# Wozblaster_v1_2.net
KiCad netlist of a schematic drawn in EAGLE
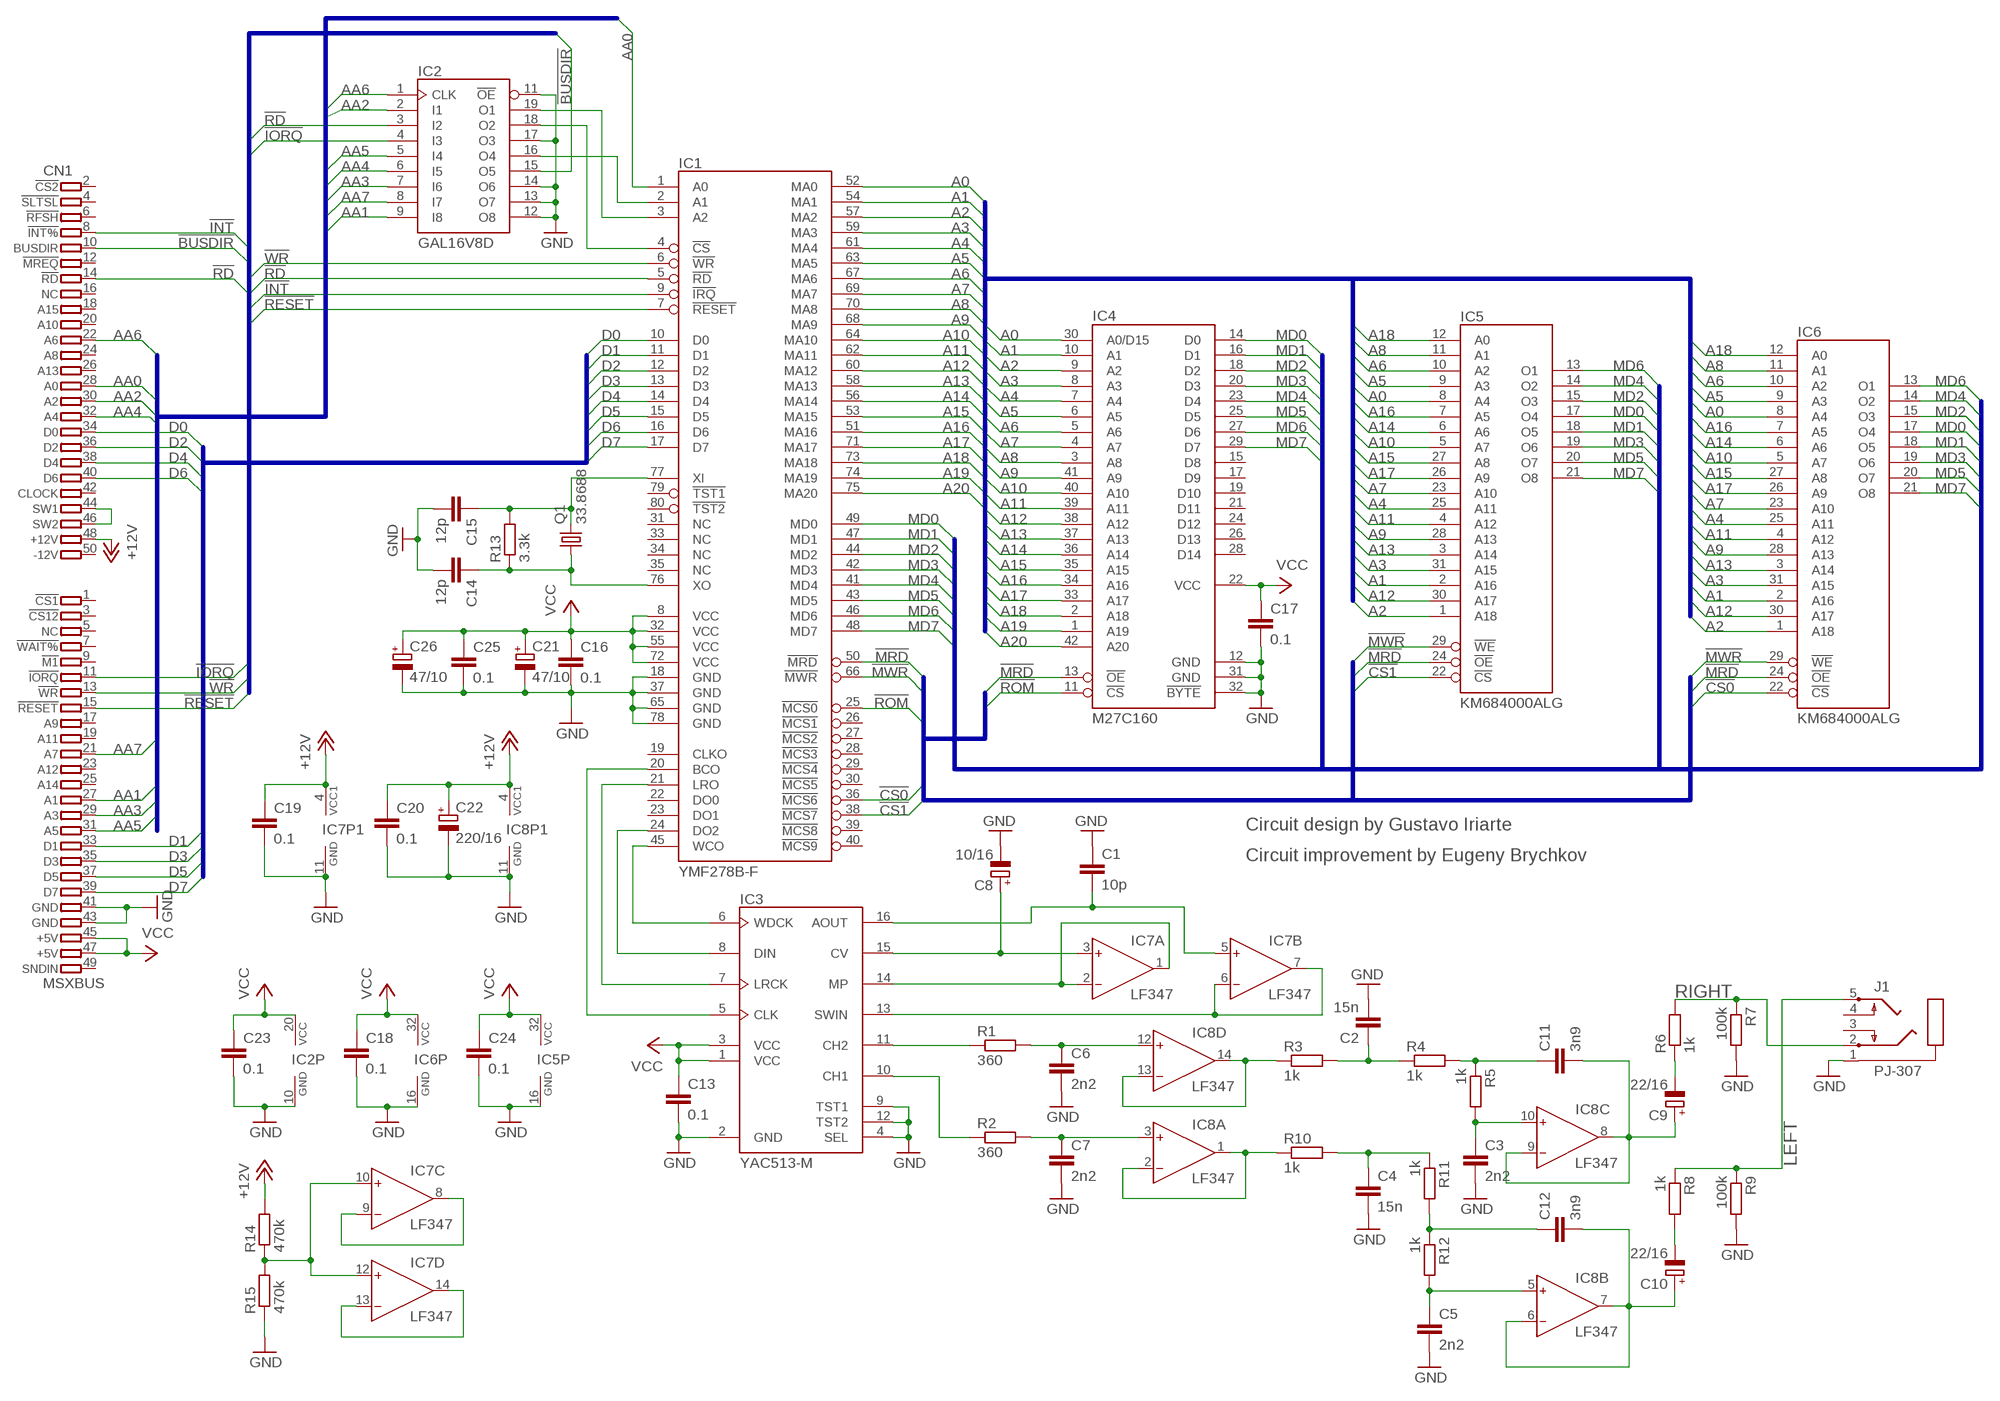
[diagram p0: schematic, sheet 1]

(export (version "E")
  (design (tool "Eeschema 10.0.6"))
  (components
    (comp (ref "C1")
      (value "10p")
      (footprint "eagle-import:C0805")
      (libsource (lib "eagle-import") (part "C-EU"))
    )
    (comp (ref "C2")
      (value "15n")
      (footprint "eagle-import:C0805")
      (libsource (lib "eagle-import") (part "C-EU"))
    )
    (comp (ref "C3")
      (value "2n2")
      (footprint "eagle-import:C0805")
      (libsource (lib "eagle-import") (part "C-EU"))
    )
    (comp (ref "C4")
      (value "15n")
      (footprint "eagle-import:C0805")
      (libsource (lib "eagle-import") (part "C-EU"))
    )
    (comp (ref "C5")
      (value "2n2")
      (footprint "eagle-import:C0805")
      (libsource (lib "eagle-import") (part "C-EU"))
    )
    (comp (ref "C6")
      (value "2n2")
      (footprint "eagle-import:C0805")
      (libsource (lib "eagle-import") (part "C-EU"))
    )
    (comp (ref "C7")
      (value "2n2")
      (footprint "eagle-import:C0805")
      (libsource (lib "eagle-import") (part "C-EU"))
    )
    (comp (ref "C8")
      (value "10/16")
      (footprint "eagle-import:SMC_B")
      (libsource (lib "eagle-import") (part "CPOLSMCB"))
    )
    (comp (ref "C9")
      (value "22/16")
      (footprint "eagle-import:SMC_B")
      (libsource (lib "eagle-import") (part "CPOLSMCB"))
    )
    (comp (ref "C10")
      (value "22/16")
      (footprint "eagle-import:SMC_B")
      (libsource (lib "eagle-import") (part "CPOLSMCB"))
    )
    (comp (ref "C11")
      (value "3n9")
      (footprint "eagle-import:C0805")
      (libsource (lib "eagle-import") (part "C-EU"))
    )
    (comp (ref "C12")
      (value "3n9")
      (footprint "eagle-import:C0805")
      (libsource (lib "eagle-import") (part "C-EU"))
    )
    (comp (ref "C13")
      (value "0.1")
      (footprint "eagle-import:C0805")
      (libsource (lib "eagle-import") (part "C-EU"))
    )
    (comp (ref "C14")
      (value "12p")
      (footprint "eagle-import:C0805")
      (libsource (lib "eagle-import") (part "C-EU"))
    )
    (comp (ref "C15")
      (value "12p")
      (footprint "eagle-import:C0805")
      (libsource (lib "eagle-import") (part "C-EU"))
    )
    (comp (ref "C16")
      (value "0.1")
      (footprint "eagle-import:C0805")
      (libsource (lib "eagle-import") (part "C-EU"))
    )
    (comp (ref "C17")
      (value "0.1")
      (footprint "eagle-import:C0805")
      (libsource (lib "eagle-import") (part "C-EU"))
    )
    (comp (ref "C18")
      (value "0.1")
      (footprint "eagle-import:C0805")
      (libsource (lib "eagle-import") (part "C-EU"))
    )
    (comp (ref "C19")
      (value "0.1")
      (footprint "eagle-import:C0805")
      (libsource (lib "eagle-import") (part "C-EU"))
    )
    (comp (ref "C20")
      (value "0.1")
      (footprint "eagle-import:C0805")
      (libsource (lib "eagle-import") (part "C-EU"))
    )
    (comp (ref "C21")
      (value "47/10")
      (footprint "eagle-import:SMC_B")
      (libsource (lib "eagle-import") (part "CPOLSMCB"))
    )
    (comp (ref "C22")
      (value "220/16")
      (footprint "eagle-import:SMC_E")
      (libsource (lib "eagle-import") (part "CPOLSMCE"))
    )
    (comp (ref "C23")
      (value "0.1")
      (footprint "eagle-import:C0805")
      (libsource (lib "eagle-import") (part "C-EU"))
    )
    (comp (ref "C24")
      (value "0.1")
      (footprint "eagle-import:C0805")
      (libsource (lib "eagle-import") (part "C-EU"))
    )
    (comp (ref "C25")
      (value "0.1")
      (footprint "eagle-import:C0805")
      (libsource (lib "eagle-import") (part "C-EU"))
    )
    (comp (ref "C26")
      (value "47/10")
      (footprint "eagle-import:SMC_B")
      (libsource (lib "eagle-import") (part "CPOLSMCB"))
    )
    (comp (ref "CN1")
      (value "MSXBUS")
      (footprint "eagle-import:MSXBUS_EDGECONN")
      (libsource (lib "eagle-import") (part "MSXBUS_EDGE"))
    )
    (comp (ref "IC1")
      (value "YMF278B-F")
      (footprint "eagle-import:80-QFP")
      (libsource (lib "eagle-import") (part "YMF278B-F"))
    )
    (comp (ref "IC2")
      (value "GAL16V8D")
      (footprint "eagle-import:DIL20")
      (libsource (lib "eagle-import") (part "GAL16V8P3"))
    )
    (comp (ref "IC3")
      (value "YAC513-M")
      (footprint "eagle-import:16SOP")
      (libsource (lib "eagle-import") (part "YAC513-M"))
    )
    (comp (ref "IC4")
      (value "M27C160")
      (footprint "eagle-import:DIL42")
      (libsource (lib "eagle-import") (part "M27C160"))
    )
    (comp (ref "IC5")
      (value "KM684000ALG")
      (footprint "eagle-import:SOP32L")
      (libsource (lib "eagle-import") (part "SRAM4MBIT"))
    )
    (comp (ref "IC6")
      (value "KM684000ALG")
      (footprint "eagle-import:SOP32L")
      (libsource (lib "eagle-import") (part "SRAM4MBIT"))
    )
    (comp (ref "IC7")
      (value "LF347")
      (footprint "eagle-import:SO14-2")
      (libsource (lib "eagle-import") (part "LF347SO14"))
    )
    (comp (ref "IC8")
      (value "LF347")
      (footprint "eagle-import:SO14-2")
      (libsource (lib "eagle-import") (part "LF347SO14"))
    )
    (comp (ref "J1")
      (value "PJ-307")
      (footprint "eagle-import:PJ-307")
      (libsource (lib "eagle-import") (part "PJ-307"))
    )
    (comp (ref "Q1")
      (value "33.8688")
      (footprint "eagle-import:HC49_S")
      (libsource (lib "eagle-import") (part "CRYSTALHC49S"))
    )
    (comp (ref "R1")
      (value "360")
      (footprint "eagle-import:R0805")
      (libsource (lib "eagle-import") (part "R-EU"))
    )
    (comp (ref "R2")
      (value "360")
      (footprint "eagle-import:R0805")
      (libsource (lib "eagle-import") (part "R-EU"))
    )
    (comp (ref "R3")
      (value "1k")
      (footprint "eagle-import:R0805")
      (libsource (lib "eagle-import") (part "R-EU"))
    )
    (comp (ref "R4")
      (value "1k")
      (footprint "eagle-import:R0805")
      (libsource (lib "eagle-import") (part "R-EU"))
    )
    (comp (ref "R5")
      (value "1k")
      (footprint "eagle-import:R0805")
      (libsource (lib "eagle-import") (part "R-EU"))
    )
    (comp (ref "R6")
      (value "1k")
      (footprint "eagle-import:R0805")
      (libsource (lib "eagle-import") (part "R-EU"))
    )
    (comp (ref "R7")
      (value "100k")
      (footprint "eagle-import:R0805")
      (libsource (lib "eagle-import") (part "R-EU"))
    )
    (comp (ref "R8")
      (value "1k")
      (footprint "eagle-import:R0805")
      (libsource (lib "eagle-import") (part "R-EU"))
    )
    (comp (ref "R9")
      (value "100k")
      (footprint "eagle-import:R0805")
      (libsource (lib "eagle-import") (part "R-EU"))
    )
    (comp (ref "R10")
      (value "1k")
      (footprint "eagle-import:R0805")
      (libsource (lib "eagle-import") (part "R-EU"))
    )
    (comp (ref "R11")
      (value "1k")
      (footprint "eagle-import:R0805")
      (libsource (lib "eagle-import") (part "R-EU"))
    )
    (comp (ref "R12")
      (value "1k")
      (footprint "eagle-import:R0805")
      (libsource (lib "eagle-import") (part "R-EU"))
    )
    (comp (ref "R13")
      (value "3.3k")
      (footprint "eagle-import:R0805")
      (libsource (lib "eagle-import") (part "R-EU"))
    )
    (comp (ref "R14")
      (value "470k")
      (footprint "eagle-import:R0805")
      (libsource (lib "eagle-import") (part "R-EU"))
    )
    (comp (ref "R15")
      (value "470k")
      (footprint "eagle-import:R0805")
      (libsource (lib "eagle-import") (part "R-EU"))
    )
  )
  (nets
    (net (code "1") (name "+12V") (class "Default")
      (node (ref "C19") (pin "1") (pinfunction "1_1") (pintype "passive"))
      (node (ref "C20") (pin "1") (pinfunction "1_1") (pintype "passive"))
      (node (ref "C22") (pin "+") (pinfunction "+_+") (pintype "passive"))
      (node (ref "CN1") (pin "48") (pinfunction "48.+12V_48") (pintype "passive"))
      (node (ref "IC7") (pin "4") (pinfunction "VCC_4") (pintype "power_in"))
      (node (ref "IC8") (pin "4") (pinfunction "VCC_4") (pintype "power_in"))
      (node (ref "R14") (pin "2") (pinfunction "2_2") (pintype "passive"))
    )
    (net (code "2") (name "/A0") (class "Default")
      (node (ref "IC1") (pin "52") (pinfunction "MA0_52") (pintype "output"))
      (node (ref "IC4") (pin "30") (pinfunction "A0/D15_30") (pintype "passive"))
      (node (ref "IC5") (pin "8") (pinfunction "A4_8") (pintype "bidirectional"))
      (node (ref "IC6") (pin "8") (pinfunction "A4_8") (pintype "bidirectional"))
    )
    (net (code "3") (name "/A1") (class "Default")
      (node (ref "IC1") (pin "54") (pinfunction "MA1_54") (pintype "output"))
      (node (ref "IC4") (pin "10") (pinfunction "A1_10") (pintype "passive"))
      (node (ref "IC5") (pin "2") (pinfunction "A16_2") (pintype "bidirectional"))
      (node (ref "IC6") (pin "2") (pinfunction "A16_2") (pintype "bidirectional"))
    )
    (net (code "4") (name "/A2") (class "Default")
      (node (ref "IC1") (pin "57") (pinfunction "MA2_57") (pintype "output"))
      (node (ref "IC4") (pin "9") (pinfunction "A2_9") (pintype "passive"))
      (node (ref "IC5") (pin "1") (pinfunction "A18_1") (pintype "bidirectional"))
      (node (ref "IC6") (pin "1") (pinfunction "A18_1") (pintype "bidirectional"))
    )
    (net (code "5") (name "/A3") (class "Default")
      (node (ref "IC1") (pin "59") (pinfunction "MA3_59") (pintype "output"))
      (node (ref "IC4") (pin "8") (pinfunction "A3_8") (pintype "passive"))
      (node (ref "IC5") (pin "31") (pinfunction "A15_31") (pintype "bidirectional"))
      (node (ref "IC6") (pin "31") (pinfunction "A15_31") (pintype "bidirectional"))
    )
    (net (code "6") (name "/A4") (class "Default")
      (node (ref "IC1") (pin "61") (pinfunction "MA4_61") (pintype "output"))
      (node (ref "IC4") (pin "7") (pinfunction "A4_7") (pintype "passive"))
      (node (ref "IC5") (pin "25") (pinfunction "A11_25") (pintype "bidirectional"))
      (node (ref "IC6") (pin "25") (pinfunction "A11_25") (pintype "bidirectional"))
    )
    (net (code "7") (name "/A5") (class "Default")
      (node (ref "IC1") (pin "63") (pinfunction "MA5_63") (pintype "output"))
      (node (ref "IC4") (pin "6") (pinfunction "A5_6") (pintype "passive"))
      (node (ref "IC5") (pin "9") (pinfunction "A3_9") (pintype "bidirectional"))
      (node (ref "IC6") (pin "9") (pinfunction "A3_9") (pintype "bidirectional"))
    )
    (net (code "8") (name "/A6") (class "Default")
      (node (ref "IC1") (pin "67") (pinfunction "MA6_67") (pintype "output"))
      (node (ref "IC4") (pin "5") (pinfunction "A6_5") (pintype "passive"))
      (node (ref "IC5") (pin "10") (pinfunction "A2_10") (pintype "bidirectional"))
      (node (ref "IC6") (pin "10") (pinfunction "A2_10") (pintype "bidirectional"))
    )
    (net (code "9") (name "/A7") (class "Default")
      (node (ref "IC1") (pin "69") (pinfunction "MA7_69") (pintype "output"))
      (node (ref "IC4") (pin "4") (pinfunction "A7_4") (pintype "passive"))
      (node (ref "IC5") (pin "23") (pinfunction "A10_23") (pintype "bidirectional"))
      (node (ref "IC6") (pin "23") (pinfunction "A10_23") (pintype "bidirectional"))
    )
    (net (code "10") (name "/A8") (class "Default")
      (node (ref "IC1") (pin "70") (pinfunction "MA8_70") (pintype "output"))
      (node (ref "IC4") (pin "3") (pinfunction "A8_3") (pintype "passive"))
      (node (ref "IC5") (pin "11") (pinfunction "A1_11") (pintype "bidirectional"))
      (node (ref "IC6") (pin "11") (pinfunction "A1_11") (pintype "bidirectional"))
    )
    (net (code "11") (name "/A9") (class "Default")
      (node (ref "IC1") (pin "68") (pinfunction "MA9_68") (pintype "output"))
      (node (ref "IC4") (pin "41") (pinfunction "A9_41") (pintype "passive"))
      (node (ref "IC5") (pin "28") (pinfunction "A13_28") (pintype "bidirectional"))
      (node (ref "IC6") (pin "28") (pinfunction "A13_28") (pintype "bidirectional"))
    )
    (net (code "12") (name "/A10") (class "Default")
      (node (ref "IC1") (pin "64") (pinfunction "MA10_64") (pintype "output"))
      (node (ref "IC4") (pin "40") (pinfunction "A10_40") (pintype "passive"))
      (node (ref "IC5") (pin "5") (pinfunction "A7_5") (pintype "bidirectional"))
      (node (ref "IC6") (pin "5") (pinfunction "A7_5") (pintype "bidirectional"))
    )
    (net (code "13") (name "/A11") (class "Default")
      (node (ref "IC1") (pin "62") (pinfunction "MA11_62") (pintype "output"))
      (node (ref "IC4") (pin "39") (pinfunction "A11_39") (pintype "passive"))
      (node (ref "IC5") (pin "4") (pinfunction "A12_4") (pintype "bidirectional"))
      (node (ref "IC6") (pin "4") (pinfunction "A12_4") (pintype "bidirectional"))
    )
    (net (code "14") (name "/A12") (class "Default")
      (node (ref "IC1") (pin "60") (pinfunction "MA12_60") (pintype "output"))
      (node (ref "IC4") (pin "38") (pinfunction "A12_38") (pintype "passive"))
      (node (ref "IC5") (pin "30") (pinfunction "A17_30") (pintype "bidirectional"))
      (node (ref "IC6") (pin "30") (pinfunction "A17_30") (pintype "bidirectional"))
    )
    (net (code "15") (name "/A13") (class "Default")
      (node (ref "IC1") (pin "58") (pinfunction "MA13_58") (pintype "output"))
      (node (ref "IC4") (pin "37") (pinfunction "A13_37") (pintype "passive"))
      (node (ref "IC5") (pin "3") (pinfunction "A14_3") (pintype "bidirectional"))
      (node (ref "IC6") (pin "3") (pinfunction "A14_3") (pintype "bidirectional"))
    )
    (net (code "16") (name "/A14") (class "Default")
      (node (ref "IC1") (pin "56") (pinfunction "MA14_56") (pintype "output"))
      (node (ref "IC4") (pin "36") (pinfunction "A14_36") (pintype "passive"))
      (node (ref "IC5") (pin "6") (pinfunction "A6_6") (pintype "bidirectional"))
      (node (ref "IC6") (pin "6") (pinfunction "A6_6") (pintype "bidirectional"))
    )
    (net (code "17") (name "/A15") (class "Default")
      (node (ref "IC1") (pin "53") (pinfunction "MA15_53") (pintype "output"))
      (node (ref "IC4") (pin "35") (pinfunction "A15_35") (pintype "passive"))
      (node (ref "IC5") (pin "27") (pinfunction "A8_27") (pintype "bidirectional"))
      (node (ref "IC6") (pin "27") (pinfunction "A8_27") (pintype "bidirectional"))
    )
    (net (code "18") (name "/A16") (class "Default")
      (node (ref "IC1") (pin "51") (pinfunction "MA16_51") (pintype "output"))
      (node (ref "IC4") (pin "34") (pinfunction "A16_34") (pintype "passive"))
      (node (ref "IC5") (pin "7") (pinfunction "A5_7") (pintype "bidirectional"))
      (node (ref "IC6") (pin "7") (pinfunction "A5_7") (pintype "bidirectional"))
    )
    (net (code "19") (name "/A17") (class "Default")
      (node (ref "IC1") (pin "71") (pinfunction "MA17_71") (pintype "output"))
      (node (ref "IC4") (pin "33") (pinfunction "A17_33") (pintype "passive"))
      (node (ref "IC5") (pin "26") (pinfunction "A9_26") (pintype "bidirectional"))
      (node (ref "IC6") (pin "26") (pinfunction "A9_26") (pintype "bidirectional"))
    )
    (net (code "20") (name "/A18") (class "Default")
      (node (ref "IC1") (pin "73") (pinfunction "MA18_73") (pintype "output"))
      (node (ref "IC4") (pin "2") (pinfunction "A18_2") (pintype "passive"))
      (node (ref "IC5") (pin "12") (pinfunction "A0_12") (pintype "bidirectional"))
      (node (ref "IC6") (pin "12") (pinfunction "A0_12") (pintype "bidirectional"))
    )
    (net (code "21") (name "/A19") (class "Default")
      (node (ref "IC1") (pin "74") (pinfunction "MA19_74") (pintype "output"))
      (node (ref "IC4") (pin "1") (pinfunction "A19_1") (pintype "passive"))
    )
    (net (code "22") (name "/A20") (class "Default")
      (node (ref "IC1") (pin "75") (pinfunction "MA20_75") (pintype "output"))
      (node (ref "IC4") (pin "42") (pinfunction "A20_42") (pintype "passive"))
    )
    (net (code "23") (name "/AA0") (class "Default")
      (node (ref "CN1") (pin "28") (pinfunction "28.A0_28") (pintype "output"))
      (node (ref "IC1") (pin "1") (pinfunction "A0_1") (pintype "input"))
    )
    (net (code "24") (name "/AA1") (class "Default")
      (node (ref "CN1") (pin "27") (pinfunction "27.A1_27") (pintype "output"))
      (node (ref "IC2") (pin "9") (pinfunction "I8_9") (pintype "input"))
    )
    (net (code "25") (name "/AA2") (class "Default")
      (node (ref "CN1") (pin "30") (pinfunction "30.A2_30") (pintype "output"))
      (node (ref "IC2") (pin "2") (pinfunction "I1_2") (pintype "input"))
    )
    (net (code "26") (name "/AA3") (class "Default")
      (node (ref "CN1") (pin "29") (pinfunction "29.A3_29") (pintype "output"))
      (node (ref "IC2") (pin "7") (pinfunction "I6_7") (pintype "input"))
    )
    (net (code "27") (name "/AA4") (class "Default")
      (node (ref "CN1") (pin "32") (pinfunction "32.A4_32") (pintype "output"))
      (node (ref "IC2") (pin "6") (pinfunction "I5_6") (pintype "input"))
    )
    (net (code "28") (name "/AA5") (class "Default")
      (node (ref "CN1") (pin "31") (pinfunction "31.A5_31") (pintype "output"))
      (node (ref "IC2") (pin "5") (pinfunction "I4_5") (pintype "input"))
    )
    (net (code "29") (name "/AA6") (class "Default")
      (node (ref "CN1") (pin "22") (pinfunction "22.A6_22") (pintype "output"))
      (node (ref "IC2") (pin "1") (pinfunction "CLK_1") (pintype "input"))
    )
    (net (code "30") (name "/AA7") (class "Default")
      (node (ref "CN1") (pin "21") (pinfunction "21.A7_21") (pintype "output"))
      (node (ref "IC2") (pin "8") (pinfunction "I7_8") (pintype "input"))
    )
    (net (code "31") (name "/D0") (class "Default")
      (node (ref "CN1") (pin "34") (pinfunction "34.D0_34") (pintype "bidirectional"))
      (node (ref "IC1") (pin "10") (pinfunction "D0_10") (pintype "bidirectional"))
    )
    (net (code "32") (name "/D1") (class "Default")
      (node (ref "CN1") (pin "33") (pinfunction "33.D1_33") (pintype "bidirectional"))
      (node (ref "IC1") (pin "11") (pinfunction "D1_11") (pintype "bidirectional"))
    )
    (net (code "33") (name "/D2") (class "Default")
      (node (ref "CN1") (pin "36") (pinfunction "36.D2_36") (pintype "bidirectional"))
      (node (ref "IC1") (pin "12") (pinfunction "D2_12") (pintype "bidirectional"))
    )
    (net (code "34") (name "/D3") (class "Default")
      (node (ref "CN1") (pin "35") (pinfunction "35.D3_35") (pintype "bidirectional"))
      (node (ref "IC1") (pin "13") (pinfunction "D3_13") (pintype "bidirectional"))
    )
    (net (code "35") (name "/D4") (class "Default")
      (node (ref "CN1") (pin "38") (pinfunction "38.D4_38") (pintype "bidirectional"))
      (node (ref "IC1") (pin "14") (pinfunction "D4_14") (pintype "bidirectional"))
    )
    (net (code "36") (name "/D5") (class "Default")
      (node (ref "CN1") (pin "37") (pinfunction "37.D5_37") (pintype "bidirectional"))
      (node (ref "IC1") (pin "15") (pinfunction "D5_15") (pintype "bidirectional"))
    )
    (net (code "37") (name "/D6") (class "Default")
      (node (ref "CN1") (pin "40") (pinfunction "40.D6_40") (pintype "bidirectional"))
      (node (ref "IC1") (pin "16") (pinfunction "D6_16") (pintype "bidirectional"))
    )
    (net (code "38") (name "/D7") (class "Default")
      (node (ref "CN1") (pin "39") (pinfunction "39.D7_39") (pintype "bidirectional"))
      (node (ref "IC1") (pin "17") (pinfunction "D7_17") (pintype "bidirectional"))
    )
    (net (code "39") (name "/MD0") (class "Default")
      (node (ref "IC1") (pin "49") (pinfunction "MD0_49") (pintype "bidirectional"))
      (node (ref "IC4") (pin "14") (pinfunction "D0_14") (pintype "passive"))
      (node (ref "IC5") (pin "17") (pinfunction "O4_17") (pintype "bidirectional"))
      (node (ref "IC6") (pin "17") (pinfunction "O4_17") (pintype "bidirectional"))
    )
    (net (code "40") (name "/MD1") (class "Default")
      (node (ref "IC1") (pin "47") (pinfunction "MD1_47") (pintype "bidirectional"))
      (node (ref "IC4") (pin "16") (pinfunction "D1_16") (pintype "passive"))
      (node (ref "IC5") (pin "18") (pinfunction "O5_18") (pintype "bidirectional"))
      (node (ref "IC6") (pin "18") (pinfunction "O5_18") (pintype "bidirectional"))
    )
    (net (code "41") (name "/MD2") (class "Default")
      (node (ref "IC1") (pin "44") (pinfunction "MD2_44") (pintype "bidirectional"))
      (node (ref "IC4") (pin "18") (pinfunction "D2_18") (pintype "passive"))
      (node (ref "IC5") (pin "15") (pinfunction "O3_15") (pintype "bidirectional"))
      (node (ref "IC6") (pin "15") (pinfunction "O3_15") (pintype "bidirectional"))
    )
    (net (code "42") (name "/MD3") (class "Default")
      (node (ref "IC1") (pin "42") (pinfunction "MD3_42") (pintype "bidirectional"))
      (node (ref "IC4") (pin "20") (pinfunction "D3_20") (pintype "passive"))
      (node (ref "IC5") (pin "19") (pinfunction "O6_19") (pintype "bidirectional"))
      (node (ref "IC6") (pin "19") (pinfunction "O6_19") (pintype "bidirectional"))
    )
    (net (code "43") (name "/MD4") (class "Default")
      (node (ref "IC1") (pin "41") (pinfunction "MD4_41") (pintype "bidirectional"))
      (node (ref "IC4") (pin "23") (pinfunction "D4_23") (pintype "passive"))
      (node (ref "IC5") (pin "14") (pinfunction "O2_14") (pintype "bidirectional"))
      (node (ref "IC6") (pin "14") (pinfunction "O2_14") (pintype "bidirectional"))
    )
    (net (code "44") (name "/MD5") (class "Default")
      (node (ref "IC1") (pin "43") (pinfunction "MD5_43") (pintype "bidirectional"))
      (node (ref "IC4") (pin "25") (pinfunction "D5_25") (pintype "passive"))
      (node (ref "IC5") (pin "20") (pinfunction "O7_20") (pintype "bidirectional"))
      (node (ref "IC6") (pin "20") (pinfunction "O7_20") (pintype "bidirectional"))
    )
    (net (code "45") (name "/MD6") (class "Default")
      (node (ref "IC1") (pin "46") (pinfunction "MD6_46") (pintype "bidirectional"))
      (node (ref "IC4") (pin "27") (pinfunction "D6_27") (pintype "passive"))
      (node (ref "IC5") (pin "13") (pinfunction "O1_13") (pintype "bidirectional"))
      (node (ref "IC6") (pin "13") (pinfunction "O1_13") (pintype "bidirectional"))
    )
    (net (code "46") (name "/MD7") (class "Default")
      (node (ref "IC1") (pin "48") (pinfunction "MD7_48") (pintype "bidirectional"))
      (node (ref "IC4") (pin "29") (pinfunction "D7_29") (pintype "passive"))
      (node (ref "IC5") (pin "21") (pinfunction "O8_21") (pintype "bidirectional"))
      (node (ref "IC6") (pin "21") (pinfunction "O8_21") (pintype "bidirectional"))
    )
    (net (code "47") (name "/~{BUSDIR}") (class "Default")
      (node (ref "CN1") (pin "10") (pinfunction "10.BUSDIR_10") (pintype "open_collector"))
      (node (ref "IC2") (pin "15") (pinfunction "O5_15") (pintype "tri_state"))
    )
    (net (code "48") (name "/~{CS0}") (class "Default")
      (node (ref "IC1") (pin "36") (pinfunction "~{MCS6}_36") (pintype "output"))
      (node (ref "IC6") (pin "22") (pinfunction "~{CS}_22") (pintype "bidirectional"))
    )
    (net (code "49") (name "/~{CS1}") (class "Default")
      (node (ref "IC1") (pin "38") (pinfunction "~{MCS7}_38") (pintype "output"))
      (node (ref "IC5") (pin "22") (pinfunction "~{CS}_22") (pintype "bidirectional"))
    )
    (net (code "50") (name "/~{INT}") (class "Default")
      (node (ref "CN1") (pin "8") (pinfunction "8.~{INT%}_8") (pintype "open_collector"))
      (node (ref "IC1") (pin "9") (pinfunction "~{IRQ}_9") (pintype "bidirectional"))
    )
    (net (code "51") (name "/~{IORQ}") (class "Default")
      (node (ref "CN1") (pin "11") (pinfunction "11.~{IORQ}_11") (pintype "output"))
      (node (ref "IC2") (pin "4") (pinfunction "I3_4") (pintype "input"))
    )
    (net (code "52") (name "/~{MRD}") (class "Default")
      (node (ref "IC1") (pin "50") (pinfunction "~{MRD}_50") (pintype "output"))
      (node (ref "IC4") (pin "13") (pinfunction "~{OE}_13") (pintype "passive"))
      (node (ref "IC5") (pin "24") (pinfunction "~{OE}_24") (pintype "bidirectional"))
      (node (ref "IC6") (pin "24") (pinfunction "~{OE}_24") (pintype "bidirectional"))
    )
    (net (code "53") (name "/~{MWR}") (class "Default")
      (node (ref "IC1") (pin "66") (pinfunction "~{MWR}_66") (pintype "output"))
      (node (ref "IC5") (pin "29") (pinfunction "~{WE}_29") (pintype "bidirectional"))
      (node (ref "IC6") (pin "29") (pinfunction "~{WE}_29") (pintype "bidirectional"))
    )
    (net (code "54") (name "/~{RD}") (class "Default")
      (node (ref "CN1") (pin "14") (pinfunction "14.~{RD}_14") (pintype "output"))
      (node (ref "IC1") (pin "5") (pinfunction "~{RD}_5") (pintype "input"))
      (node (ref "IC2") (pin "3") (pinfunction "I2_3") (pintype "input"))
    )
    (net (code "55") (name "/~{RESET}") (class "Default")
      (node (ref "CN1") (pin "15") (pinfunction "15.~{RESET}_15") (pintype "output"))
      (node (ref "IC1") (pin "7") (pinfunction "~{RESET}_7") (pintype "input"))
    )
    (net (code "56") (name "/~{ROM}") (class "Default")
      (node (ref "IC1") (pin "25") (pinfunction "~{MCS0}_25") (pintype "output"))
      (node (ref "IC4") (pin "11") (pinfunction "~{CS}_11") (pintype "passive"))
    )
    (net (code "57") (name "/~{WR}") (class "Default")
      (node (ref "CN1") (pin "13") (pinfunction "13.~{WR}_13") (pintype "output"))
      (node (ref "IC1") (pin "6") (pinfunction "~{WR}_6") (pintype "input"))
    )
    (net (code "58") (name "GND") (class "Default")
      (node (ref "C1") (pin "1") (pinfunction "1_1") (pintype "passive"))
      (node (ref "C13") (pin "2") (pinfunction "2_2") (pintype "passive"))
      (node (ref "C14") (pin "2") (pinfunction "2_2") (pintype "passive"))
      (node (ref "C15") (pin "2") (pinfunction "2_2") (pintype "passive"))
      (node (ref "C16") (pin "2") (pinfunction "2_2") (pintype "passive"))
      (node (ref "C17") (pin "2") (pinfunction "2_2") (pintype "passive"))
      (node (ref "C18") (pin "2") (pinfunction "2_2") (pintype "passive"))
      (node (ref "C19") (pin "2") (pinfunction "2_2") (pintype "passive"))
      (node (ref "C2") (pin "2") (pinfunction "2_2") (pintype "passive"))
      (node (ref "C20") (pin "2") (pinfunction "2_2") (pintype "passive"))
      (node (ref "C21") (pin "-") (pinfunction "-_-") (pintype "passive"))
      (node (ref "C22") (pin "-") (pinfunction "-_-") (pintype "passive"))
      (node (ref "C23") (pin "2") (pinfunction "2_2") (pintype "passive"))
      (node (ref "C24") (pin "2") (pinfunction "2_2") (pintype "passive"))
      (node (ref "C25") (pin "2") (pinfunction "2_2") (pintype "passive"))
      (node (ref "C26") (pin "-") (pinfunction "-_-") (pintype "passive"))
      (node (ref "C3") (pin "2") (pinfunction "2_2") (pintype "passive"))
      (node (ref "C4") (pin "2") (pinfunction "2_2") (pintype "passive"))
      (node (ref "C5") (pin "2") (pinfunction "2_2") (pintype "passive"))
      (node (ref "C6") (pin "2") (pinfunction "2_2") (pintype "passive"))
      (node (ref "C7") (pin "2") (pinfunction "2_2") (pintype "passive"))
      (node (ref "C8") (pin "-") (pinfunction "-_-") (pintype "passive"))
      (node (ref "CN1") (pin "41") (pinfunction "41.GND_41") (pintype "passive"))
      (node (ref "CN1") (pin "43") (pinfunction "43.GND_43") (pintype "passive"))
      (node (ref "IC1") (pin "18") (pinfunction "GND_18") (pintype "bidirectional"))
      (node (ref "IC1") (pin "37") (pinfunction "GND_37") (pintype "bidirectional"))
      (node (ref "IC1") (pin "65") (pinfunction "GND_65") (pintype "bidirectional"))
      (node (ref "IC1") (pin "78") (pinfunction "GND_78") (pintype "bidirectional"))
      (node (ref "IC2") (pin "10") (pinfunction "GND_10") (pintype "power_in"))
      (node (ref "IC2") (pin "11") (pinfunction "~{OE}_11") (pintype "input"))
      (node (ref "IC2") (pin "12") (pinfunction "O8_12") (pintype "tri_state"))
      (node (ref "IC2") (pin "13") (pinfunction "O7_13") (pintype "tri_state"))
      (node (ref "IC2") (pin "14") (pinfunction "O6_14") (pintype "tri_state"))
      (node (ref "IC2") (pin "17") (pinfunction "O3_17") (pintype "tri_state"))
      (node (ref "IC3") (pin "12") (pinfunction "TST2_12") (pintype "input"))
      (node (ref "IC3") (pin "2") (pinfunction "GND_2") (pintype "power_in"))
      (node (ref "IC3") (pin "4") (pinfunction "SEL_4") (pintype "input"))
      (node (ref "IC3") (pin "9") (pinfunction "TST1_9") (pintype "input"))
      (node (ref "IC4") (pin "12") (pinfunction "GND_12") (pintype "passive"))
      (node (ref "IC4") (pin "31") (pinfunction "GND_31") (pintype "passive"))
      (node (ref "IC4") (pin "32") (pinfunction "~{BYTE}_32") (pintype "passive"))
      (node (ref "IC5") (pin "16") (pinfunction "GND_16") (pintype "power_in"))
      (node (ref "IC6") (pin "16") (pinfunction "GND_16") (pintype "power_in"))
      (node (ref "IC7") (pin "11") (pinfunction "GND_11") (pintype "power_in"))
      (node (ref "IC8") (pin "11") (pinfunction "GND_11") (pintype "power_in"))
      (node (ref "J1") (pin "1") (pinfunction "1_1") (pintype "passive"))
      (node (ref "R15") (pin "1") (pinfunction "1_1") (pintype "passive"))
      (node (ref "R7") (pin "2") (pinfunction "2_2") (pintype "passive"))
      (node (ref "R9") (pin "2") (pinfunction "2_2") (pintype "passive"))
    )
    (net (code "59") (name "Net-(C2-Pad1)") (class "Default")
      (node (ref "C2") (pin "1") (pinfunction "1_1") (pintype "passive"))
      (node (ref "R3") (pin "2") (pinfunction "2_2") (pintype "passive"))
      (node (ref "R4") (pin "1") (pinfunction "1_1") (pintype "passive"))
    )
    (net (code "60") (name "Net-(C4-Pad1)") (class "Default")
      (node (ref "C4") (pin "1") (pinfunction "1_1") (pintype "passive"))
      (node (ref "R10") (pin "2") (pinfunction "2_2") (pintype "passive"))
      (node (ref "R11") (pin "1") (pinfunction "1_1") (pintype "passive"))
    )
    (net (code "61") (name "Net-(C9-Pad-)") (class "Default")
      (node (ref "C9") (pin "-") (pinfunction "-_-") (pintype "passive"))
      (node (ref "R6") (pin "1") (pinfunction "1_1") (pintype "passive"))
    )
    (net (code "62") (name "Net-(C10-Pad-)") (class "Default")
      (node (ref "C10") (pin "-") (pinfunction "-_-") (pintype "passive"))
      (node (ref "R8") (pin "2") (pinfunction "2_2") (pintype "passive"))
    )
    (net (code "63") (name "Net-(C11-Pad1)") (class "Default")
      (node (ref "C11") (pin "1") (pinfunction "1_1") (pintype "passive"))
      (node (ref "R4") (pin "2") (pinfunction "2_2") (pintype "passive"))
      (node (ref "R5") (pin "1") (pinfunction "1_1") (pintype "passive"))
    )
    (net (code "64") (name "Net-(C12-Pad1)") (class "Default")
      (node (ref "C12") (pin "1") (pinfunction "1_1") (pintype "passive"))
      (node (ref "R11") (pin "2") (pinfunction "2_2") (pintype "passive"))
      (node (ref "R12") (pin "1") (pinfunction "1_1") (pintype "passive"))
    )
    (net (code "65") (name "Net-(CN1-44.SW1)") (class "Default")
      (node (ref "CN1") (pin "44") (pinfunction "44.SW1_44") (pintype "passive"))
      (node (ref "CN1") (pin "46") (pinfunction "46.SW2_46") (pintype "passive"))
    )
    (net (code "66") (name "Net-(IC1-A1)") (class "Default")
      (node (ref "IC1") (pin "2") (pinfunction "A1_2") (pintype "input"))
      (node (ref "IC2") (pin "16") (pinfunction "O4_16") (pintype "tri_state"))
    )
    (net (code "67") (name "Net-(IC1-A2)") (class "Default")
      (node (ref "IC1") (pin "3") (pinfunction "A2_3") (pintype "input"))
      (node (ref "IC2") (pin "19") (pinfunction "O1_19") (pintype "tri_state"))
    )
    (net (code "68") (name "Net-(IC1-BCO)") (class "Default")
      (node (ref "IC1") (pin "20") (pinfunction "BCO_20") (pintype "output"))
      (node (ref "IC3") (pin "5") (pinfunction "CLK_5") (pintype "input"))
    )
    (net (code "69") (name "Net-(IC1-DO2)") (class "Default")
      (node (ref "IC1") (pin "24") (pinfunction "DO2_24") (pintype "output"))
      (node (ref "IC3") (pin "8") (pinfunction "DIN_8") (pintype "input"))
    )
    (net (code "70") (name "Net-(IC1-LRO)") (class "Default")
      (node (ref "IC1") (pin "21") (pinfunction "LRO_21") (pintype "output"))
      (node (ref "IC3") (pin "7") (pinfunction "LRCK_7") (pintype "input"))
    )
    (net (code "71") (name "Net-(IC1-WCO)") (class "Default")
      (node (ref "IC1") (pin "45") (pinfunction "WCO_45") (pintype "output"))
      (node (ref "IC3") (pin "6") (pinfunction "WDCK_6") (pintype "input"))
    )
    (net (code "72") (name "Net-(IC1-XI)") (class "Default")
      (node (ref "C15") (pin "1") (pinfunction "1_1") (pintype "passive"))
      (node (ref "IC1") (pin "77") (pinfunction "XI_77") (pintype "input"))
      (node (ref "Q1") (pin "2") (pinfunction "2_2") (pintype "passive"))
      (node (ref "R13") (pin "2") (pinfunction "2_2") (pintype "passive"))
    )
    (net (code "73") (name "Net-(IC1-XO)") (class "Default")
      (node (ref "C14") (pin "1") (pinfunction "1_1") (pintype "passive"))
      (node (ref "IC1") (pin "76") (pinfunction "XO_76") (pintype "output"))
      (node (ref "Q1") (pin "1") (pinfunction "1_1") (pintype "passive"))
      (node (ref "R13") (pin "1") (pinfunction "1_1") (pintype "passive"))
    )
    (net (code "74") (name "Net-(IC1-~{CS})") (class "Default")
      (node (ref "IC1") (pin "4") (pinfunction "~{CS}_4") (pintype "input"))
      (node (ref "IC2") (pin "18") (pinfunction "O2_18") (pintype "tri_state"))
    )
    (net (code "75") (name "Net-(IC3-AOUT)") (class "Default")
      (node (ref "C1") (pin "2") (pinfunction "2_2") (pintype "passive"))
      (node (ref "IC3") (pin "16") (pinfunction "AOUT_16") (pintype "output"))
      (node (ref "IC7") (pin "5") (pinfunction "IN+_5") (pintype "input"))
    )
    (net (code "76") (name "Net-(IC3-CH1)") (class "Default")
      (node (ref "IC3") (pin "10") (pinfunction "CH1_10") (pintype "output"))
      (node (ref "R2") (pin "1") (pinfunction "1_1") (pintype "passive"))
    )
    (net (code "77") (name "Net-(IC3-CH2)") (class "Default")
      (node (ref "IC3") (pin "11") (pinfunction "CH2_11") (pintype "output"))
      (node (ref "R1") (pin "1") (pinfunction "1_1") (pintype "passive"))
    )
    (net (code "78") (name "Net-(IC3-CV)") (class "Default")
      (node (ref "C8") (pin "+") (pinfunction "+_+") (pintype "passive"))
      (node (ref "IC3") (pin "15") (pinfunction "CV_15") (pintype "input"))
      (node (ref "IC7") (pin "3") (pinfunction "IN+_3") (pintype "input"))
    )
    (net (code "79") (name "Net-(IC3-MP)") (class "Default")
      (node (ref "IC3") (pin "14") (pinfunction "MP_14") (pintype "input"))
      (node (ref "IC7") (pin "1") (pinfunction "OUT_1") (pintype "output"))
      (node (ref "IC7") (pin "2") (pinfunction "IN-_2") (pintype "input"))
    )
    (net (code "80") (name "Net-(IC3-SWIN)") (class "Default")
      (node (ref "IC3") (pin "13") (pinfunction "SWIN_13") (pintype "input"))
      (node (ref "IC7") (pin "6") (pinfunction "IN-_6") (pintype "input"))
      (node (ref "IC7") (pin "7") (pinfunction "OUT_7") (pintype "output"))
    )
    (net (code "81") (name "Net-(IC7C-IN+)") (class "Default")
      (node (ref "IC7") (pin "10") (pinfunction "IN+_10") (pintype "input"))
      (node (ref "IC7") (pin "12") (pinfunction "IN+_12") (pintype "input"))
      (node (ref "R14") (pin "1") (pinfunction "1_1") (pintype "passive"))
      (node (ref "R15") (pin "2") (pinfunction "2_2") (pintype "passive"))
    )
    (net (code "82") (name "Net-(IC7C-IN-)") (class "Default")
      (node (ref "IC7") (pin "8") (pinfunction "OUT_8") (pintype "output"))
      (node (ref "IC7") (pin "9") (pinfunction "IN-_9") (pintype "input"))
    )
    (net (code "83") (name "Net-(IC7D-IN-)") (class "Default")
      (node (ref "IC7") (pin "13") (pinfunction "IN-_13") (pintype "input"))
      (node (ref "IC7") (pin "14") (pinfunction "OUT_14") (pintype "output"))
    )
    (net (code "84") (name "Net-(IC8A-IN+)") (class "Default")
      (node (ref "C7") (pin "1") (pinfunction "1_1") (pintype "passive"))
      (node (ref "IC8") (pin "3") (pinfunction "IN+_3") (pintype "input"))
      (node (ref "R2") (pin "2") (pinfunction "2_2") (pintype "passive"))
    )
    (net (code "85") (name "Net-(IC8A-IN-)") (class "Default")
      (node (ref "IC8") (pin "1") (pinfunction "OUT_1") (pintype "output"))
      (node (ref "IC8") (pin "2") (pinfunction "IN-_2") (pintype "input"))
      (node (ref "R10") (pin "1") (pinfunction "1_1") (pintype "passive"))
    )
    (net (code "86") (name "Net-(IC8B-IN+)") (class "Default")
      (node (ref "C5") (pin "1") (pinfunction "1_1") (pintype "passive"))
      (node (ref "IC8") (pin "5") (pinfunction "IN+_5") (pintype "input"))
      (node (ref "R12") (pin "2") (pinfunction "2_2") (pintype "passive"))
    )
    (net (code "87") (name "Net-(IC8B-IN-)") (class "Default")
      (node (ref "C10") (pin "+") (pinfunction "+_+") (pintype "passive"))
      (node (ref "C12") (pin "2") (pinfunction "2_2") (pintype "passive"))
      (node (ref "IC8") (pin "6") (pinfunction "IN-_6") (pintype "input"))
      (node (ref "IC8") (pin "7") (pinfunction "OUT_7") (pintype "output"))
    )
    (net (code "88") (name "Net-(IC8C-IN+)") (class "Default")
      (node (ref "C3") (pin "1") (pinfunction "1_1") (pintype "passive"))
      (node (ref "IC8") (pin "10") (pinfunction "IN+_10") (pintype "input"))
      (node (ref "R5") (pin "2") (pinfunction "2_2") (pintype "passive"))
    )
    (net (code "89") (name "Net-(IC8C-IN-)") (class "Default")
      (node (ref "C11") (pin "2") (pinfunction "2_2") (pintype "passive"))
      (node (ref "C9") (pin "+") (pinfunction "+_+") (pintype "passive"))
      (node (ref "IC8") (pin "8") (pinfunction "OUT_8") (pintype "output"))
      (node (ref "IC8") (pin "9") (pinfunction "IN-_9") (pintype "input"))
    )
    (net (code "90") (name "Net-(IC8D-IN+)") (class "Default")
      (node (ref "C6") (pin "1") (pinfunction "1_1") (pintype "passive"))
      (node (ref "IC8") (pin "12") (pinfunction "IN+_12") (pintype "input"))
      (node (ref "R1") (pin "2") (pinfunction "2_2") (pintype "passive"))
    )
    (net (code "91") (name "Net-(IC8D-IN-)") (class "Default")
      (node (ref "IC8") (pin "13") (pinfunction "IN-_13") (pintype "input"))
      (node (ref "IC8") (pin "14") (pinfunction "OUT_14") (pintype "output"))
      (node (ref "R3") (pin "1") (pinfunction "1_1") (pintype "passive"))
    )
    (net (code "92") (name "Net-(J1-Pad2)") (class "Default")
      (node (ref "J1") (pin "2") (pinfunction "2_2") (pintype "passive"))
      (node (ref "R6") (pin "2") (pinfunction "2_2") (pintype "passive"))
      (node (ref "R7") (pin "1") (pinfunction "1_1") (pintype "passive"))
    )
    (net (code "93") (name "Net-(J1-Pad5)") (class "Default")
      (node (ref "J1") (pin "5") (pinfunction "5_5") (pintype "passive"))
      (node (ref "R8") (pin "1") (pinfunction "1_1") (pintype "passive"))
      (node (ref "R9") (pin "1") (pinfunction "1_1") (pintype "passive"))
    )
    (net (code "94") (name "VCC") (class "Default")
      (node (ref "C13") (pin "1") (pinfunction "1_1") (pintype "passive"))
      (node (ref "C16") (pin "1") (pinfunction "1_1") (pintype "passive"))
      (node (ref "C17") (pin "1") (pinfunction "1_1") (pintype "passive"))
      (node (ref "C18") (pin "1") (pinfunction "1_1") (pintype "passive"))
      (node (ref "C21") (pin "+") (pinfunction "+_+") (pintype "passive"))
      (node (ref "C23") (pin "1") (pinfunction "1_1") (pintype "passive"))
      (node (ref "C24") (pin "1") (pinfunction "1_1") (pintype "passive"))
      (node (ref "C25") (pin "1") (pinfunction "1_1") (pintype "passive"))
      (node (ref "C26") (pin "+") (pinfunction "+_+") (pintype "passive"))
      (node (ref "CN1") (pin "45") (pinfunction "45.+5V_45") (pintype "passive"))
      (node (ref "CN1") (pin "47") (pinfunction "47.+5V_47") (pintype "passive"))
      (node (ref "IC1") (pin "32") (pinfunction "VCC_32") (pintype "bidirectional"))
      (node (ref "IC1") (pin "55") (pinfunction "VCC_55") (pintype "bidirectional"))
      (node (ref "IC1") (pin "72") (pinfunction "VCC_72") (pintype "bidirectional"))
      (node (ref "IC1") (pin "8") (pinfunction "VCC_8") (pintype "bidirectional"))
      (node (ref "IC2") (pin "20") (pinfunction "VCC_20") (pintype "power_in"))
      (node (ref "IC3") (pin "1") (pinfunction "VCC_1") (pintype "power_in"))
      (node (ref "IC3") (pin "3") (pinfunction "VCC_3") (pintype "power_in"))
      (node (ref "IC4") (pin "22") (pinfunction "VCC_22") (pintype "passive"))
      (node (ref "IC5") (pin "32") (pinfunction "VCC_32") (pintype "power_in"))
      (node (ref "IC6") (pin "32") (pinfunction "VCC_32") (pintype "power_in"))
    )
    (net (code "95") (name "unconnected-(CN1-1.~{CS1}-Pad1)") (class "Default")
      (node (ref "CN1") (pin "1") (pinfunction "1.~{CS1}_1") (pintype "output"))
    )
    (net (code "96") (name "unconnected-(CN1-2.~{CS2}-Pad2)") (class "Default")
      (node (ref "CN1") (pin "2") (pinfunction "2.~{CS2}_2") (pintype "output"))
    )
    (net (code "97") (name "unconnected-(CN1-3.~{CS12}-Pad3)") (class "Default")
      (node (ref "CN1") (pin "3") (pinfunction "3.~{CS12}_3") (pintype "output"))
    )
    (net (code "98") (name "unconnected-(CN1-4.~{SLTSL}-Pad4)") (class "Default")
      (node (ref "CN1") (pin "4") (pinfunction "4.~{SLTSL}_4") (pintype "output"))
    )
    (net (code "99") (name "unconnected-(CN1-5.NC-Pad5)") (class "Default")
      (node (ref "CN1") (pin "5") (pinfunction "5.NC_5") (pintype "no_connect"))
    )
    (net (code "100") (name "unconnected-(CN1-6.~{RFSH}-Pad6)") (class "Default")
      (node (ref "CN1") (pin "6") (pinfunction "6.~{RFSH}_6") (pintype "output"))
    )
    (net (code "101") (name "unconnected-(CN1-7.~{WAIT%}-Pad7)") (class "Default")
      (node (ref "CN1") (pin "7") (pinfunction "7.~{WAIT%}_7") (pintype "open_collector"))
    )
    (net (code "102") (name "unconnected-(CN1-9.~{M1}-Pad9)") (class "Default")
      (node (ref "CN1") (pin "9") (pinfunction "9.~{M1}_9") (pintype "output"))
    )
    (net (code "103") (name "unconnected-(CN1-12.~{MREQ}-Pad12)") (class "Default")
      (node (ref "CN1") (pin "12") (pinfunction "12.~{MREQ}_12") (pintype "output"))
    )
    (net (code "104") (name "unconnected-(CN1-16.NC-Pad16)") (class "Default")
      (node (ref "CN1") (pin "16") (pinfunction "16.NC_16") (pintype "no_connect"))
    )
    (net (code "105") (name "unconnected-(CN1-17.A9-Pad17)") (class "Default")
      (node (ref "CN1") (pin "17") (pinfunction "17.A9_17") (pintype "output"))
    )
    (net (code "106") (name "unconnected-(CN1-18.A15-Pad18)") (class "Default")
      (node (ref "CN1") (pin "18") (pinfunction "18.A15_18") (pintype "output"))
    )
    (net (code "107") (name "unconnected-(CN1-19.A11-Pad19)") (class "Default")
      (node (ref "CN1") (pin "19") (pinfunction "19.A11_19") (pintype "output"))
    )
    (net (code "108") (name "unconnected-(CN1-20.A10-Pad20)") (class "Default")
      (node (ref "CN1") (pin "20") (pinfunction "20.A10_20") (pintype "output"))
    )
    (net (code "109") (name "unconnected-(CN1-23.A12-Pad23)") (class "Default")
      (node (ref "CN1") (pin "23") (pinfunction "23.A12_23") (pintype "output"))
    )
    (net (code "110") (name "unconnected-(CN1-24.A8-Pad24)") (class "Default")
      (node (ref "CN1") (pin "24") (pinfunction "24.A8_24") (pintype "output"))
    )
    (net (code "111") (name "unconnected-(CN1-25.A14-Pad25)") (class "Default")
      (node (ref "CN1") (pin "25") (pinfunction "25.A14_25") (pintype "output"))
    )
    (net (code "112") (name "unconnected-(CN1-26.A13-Pad26)") (class "Default")
      (node (ref "CN1") (pin "26") (pinfunction "26.A13_26") (pintype "output"))
    )
    (net (code "113") (name "unconnected-(CN1-42.CLOCK-Pad42)") (class "Default")
      (node (ref "CN1") (pin "42") (pinfunction "42.CLOCK_42") (pintype "output"))
    )
    (net (code "114") (name "unconnected-(CN1-49.SNDIN-Pad49)") (class "Default")
      (node (ref "CN1") (pin "49") (pinfunction "49.SNDIN_49") (pintype "open_collector"))
    )
    (net (code "115") (name "unconnected-(CN1-50.-12V-Pad50)") (class "Default")
      (node (ref "CN1") (pin "50") (pinfunction "50.-12V_50") (pintype "passive"))
    )
    (net (code "116") (name "unconnected-(IC1-CLKO-Pad19)") (class "Default")
      (node (ref "IC1") (pin "19") (pinfunction "CLKO_19") (pintype "output"))
    )
    (net (code "117") (name "unconnected-(IC1-DO0-Pad22)") (class "Default")
      (node (ref "IC1") (pin "22") (pinfunction "DO0_22") (pintype "output"))
    )
    (net (code "118") (name "unconnected-(IC1-DO1-Pad23)") (class "Default")
      (node (ref "IC1") (pin "23") (pinfunction "DO1_23") (pintype "output"))
    )
    (net (code "119") (name "unconnected-(IC1-NC-Pad31)") (class "Default")
      (node (ref "IC1") (pin "31") (pinfunction "NC_31") (pintype "no_connect"))
    )
    (net (code "120") (name "unconnected-(IC1-NC-Pad33)") (class "Default")
      (node (ref "IC1") (pin "33") (pinfunction "NC_33") (pintype "no_connect"))
    )
    (net (code "121") (name "unconnected-(IC1-NC-Pad34)") (class "Default")
      (node (ref "IC1") (pin "34") (pinfunction "NC_34") (pintype "no_connect"))
    )
    (net (code "122") (name "unconnected-(IC1-NC-Pad35)") (class "Default")
      (node (ref "IC1") (pin "35") (pinfunction "NC_35") (pintype "no_connect"))
    )
    (net (code "123") (name "unconnected-(IC1-~{MCS1}-Pad26)") (class "Default")
      (node (ref "IC1") (pin "26") (pinfunction "~{MCS1}_26") (pintype "output"))
    )
    (net (code "124") (name "unconnected-(IC1-~{MCS2}-Pad27)") (class "Default")
      (node (ref "IC1") (pin "27") (pinfunction "~{MCS2}_27") (pintype "output"))
    )
    (net (code "125") (name "unconnected-(IC1-~{MCS3}-Pad28)") (class "Default")
      (node (ref "IC1") (pin "28") (pinfunction "~{MCS3}_28") (pintype "output"))
    )
    (net (code "126") (name "unconnected-(IC1-~{MCS4}-Pad29)") (class "Default")
      (node (ref "IC1") (pin "29") (pinfunction "~{MCS4}_29") (pintype "output"))
    )
    (net (code "127") (name "unconnected-(IC1-~{MCS5}-Pad30)") (class "Default")
      (node (ref "IC1") (pin "30") (pinfunction "~{MCS5}_30") (pintype "output"))
    )
    (net (code "128") (name "unconnected-(IC1-~{MCS8}-Pad39)") (class "Default")
      (node (ref "IC1") (pin "39") (pinfunction "~{MCS8}_39") (pintype "output"))
    )
    (net (code "129") (name "unconnected-(IC1-~{MCS9}-Pad40)") (class "Default")
      (node (ref "IC1") (pin "40") (pinfunction "~{MCS9}_40") (pintype "output"))
    )
    (net (code "130") (name "unconnected-(IC1-~{TST1}-Pad79)") (class "Default")
      (node (ref "IC1") (pin "79") (pinfunction "~{TST1}_79") (pintype "passive"))
    )
    (net (code "131") (name "unconnected-(IC1-~{TST2}-Pad80)") (class "Default")
      (node (ref "IC1") (pin "80") (pinfunction "~{TST2}_80") (pintype "passive"))
    )
    (net (code "132") (name "unconnected-(IC4-D8-Pad15)") (class "Default")
      (node (ref "IC4") (pin "15") (pinfunction "D8_15") (pintype "passive"))
    )
    (net (code "133") (name "unconnected-(IC4-D9-Pad17)") (class "Default")
      (node (ref "IC4") (pin "17") (pinfunction "D9_17") (pintype "passive"))
    )
    (net (code "134") (name "unconnected-(IC4-D10-Pad19)") (class "Default")
      (node (ref "IC4") (pin "19") (pinfunction "D10_19") (pintype "passive"))
    )
    (net (code "135") (name "unconnected-(IC4-D11-Pad21)") (class "Default")
      (node (ref "IC4") (pin "21") (pinfunction "D11_21") (pintype "passive"))
    )
    (net (code "136") (name "unconnected-(IC4-D12-Pad24)") (class "Default")
      (node (ref "IC4") (pin "24") (pinfunction "D12_24") (pintype "passive"))
    )
    (net (code "137") (name "unconnected-(IC4-D13-Pad26)") (class "Default")
      (node (ref "IC4") (pin "26") (pinfunction "D13_26") (pintype "passive"))
    )
    (net (code "138") (name "unconnected-(IC4-D14-Pad28)") (class "Default")
      (node (ref "IC4") (pin "28") (pinfunction "D14_28") (pintype "passive"))
    )
    (net (code "139") (name "unconnected-(J1-Pad3)") (class "Default")
      (node (ref "J1") (pin "3") (pinfunction "3_3") (pintype "passive"))
    )
    (net (code "140") (name "unconnected-(J1-Pad4)") (class "Default")
      (node (ref "J1") (pin "4") (pinfunction "4_4") (pintype "passive"))
    )
  )
)
